# source_eagle.net
KiCad netlist of a schematic drawn in EAGLE
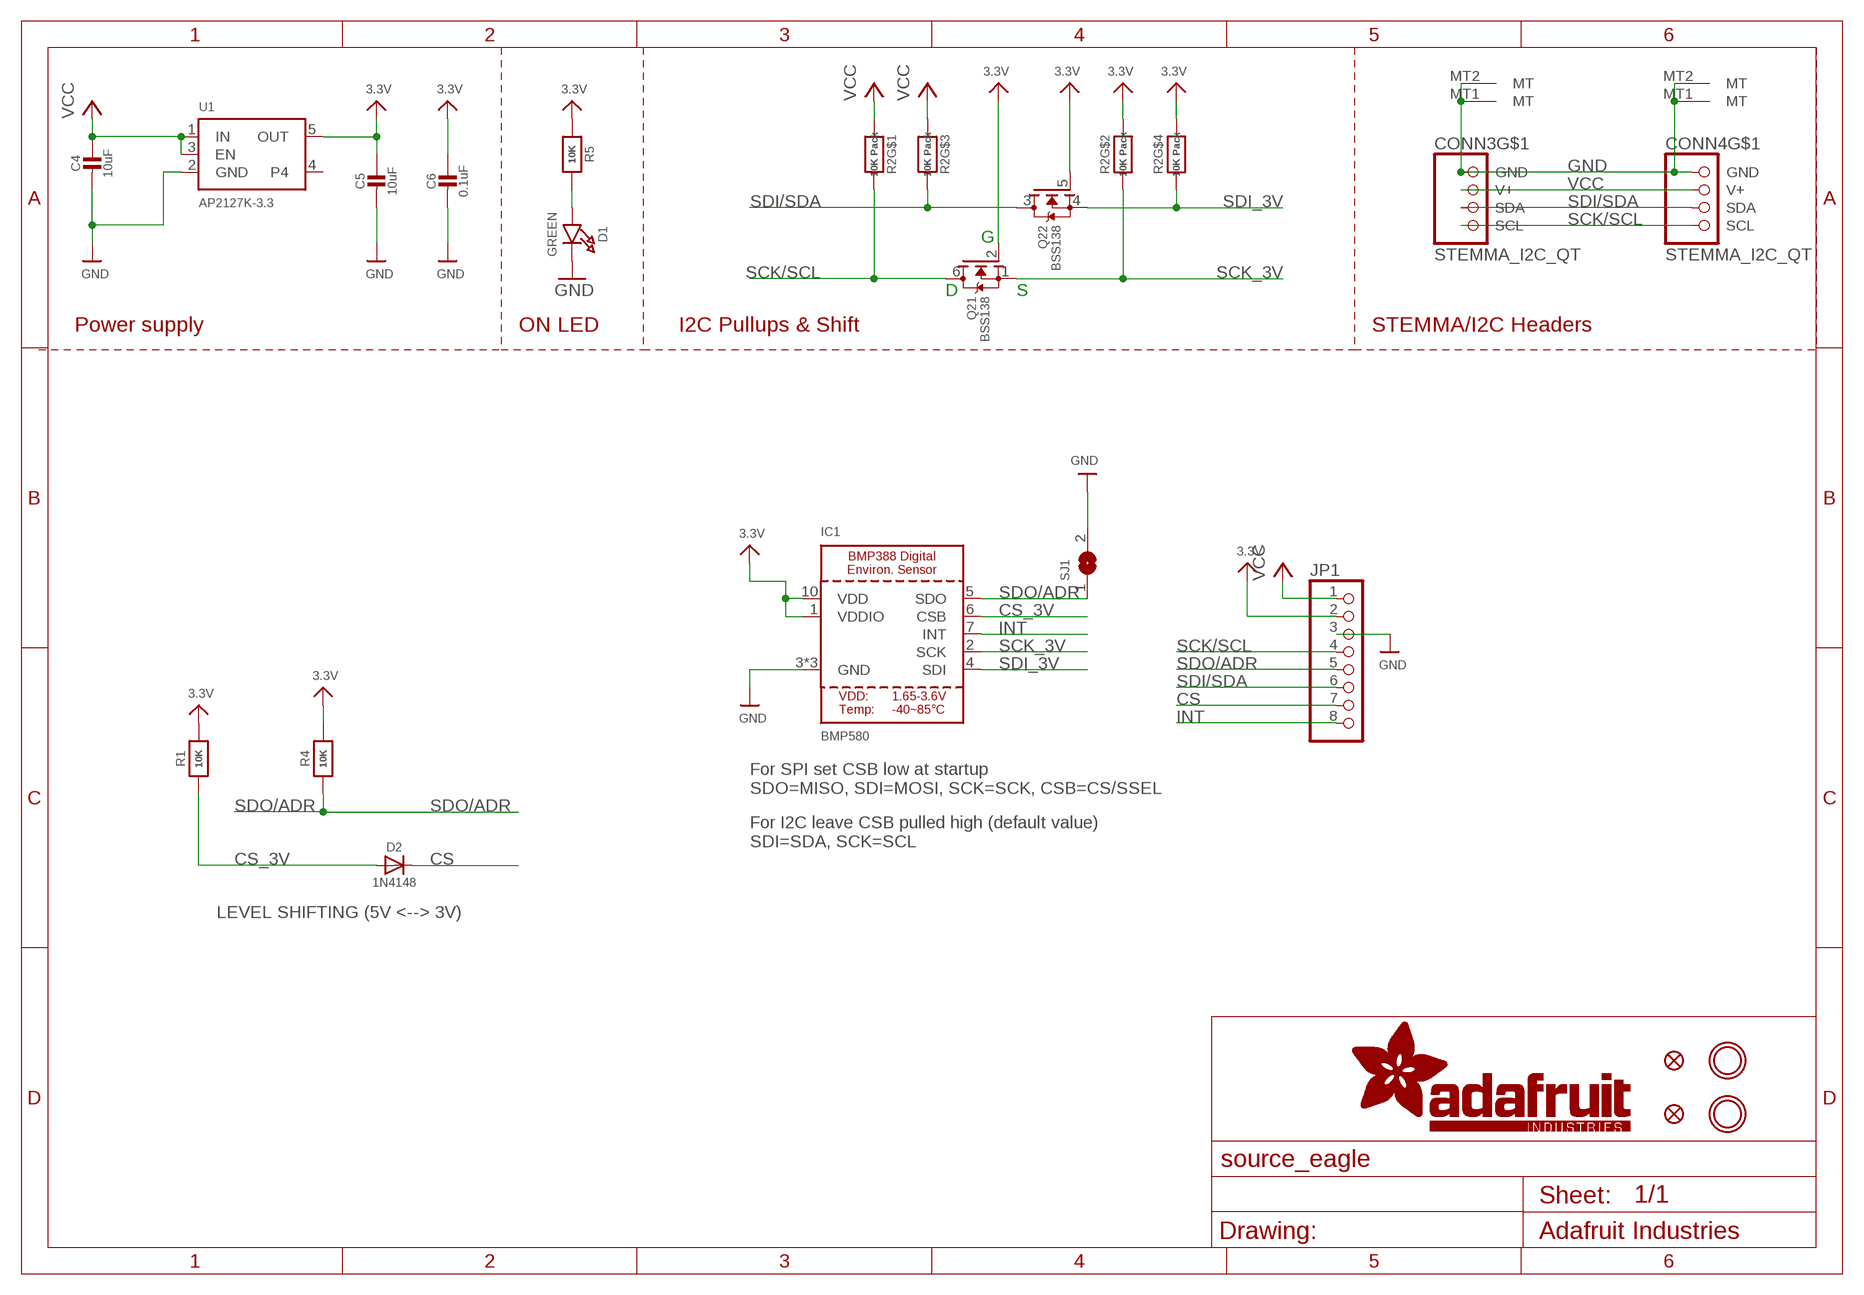
[diagram p0: schematic, sheet 1]

(export (version "E")
  (design (tool "Eeschema 10.0.6"))
  (components
    (comp (ref "C4")
      (value "10uF")
      (footprint "eagle-import:0805-NO")
      (libsource (lib "eagle-import") (part "CAP_CERAMIC0805-NOOUTLINE"))
    )
    (comp (ref "C5")
      (value "10uF")
      (footprint "eagle-import:0805-NO")
      (libsource (lib "eagle-import") (part "CAP_CERAMIC0805-NOOUTLINE"))
    )
    (comp (ref "C6")
      (value "0.1uF")
      (footprint "eagle-import:0603-NO")
      (libsource (lib "eagle-import") (part "CAP_CERAMIC0603_NO"))
    )
    (comp (ref "CONN3")
      (value "STEMMA_I2C_QT")
      (footprint "eagle-import:JST_SH4")
      (libsource (lib "eagle-import") (part "STEMMA_I2C_QT"))
    )
    (comp (ref "CONN4")
      (value "STEMMA_I2C_QT")
      (footprint "eagle-import:JST_SH4")
      (libsource (lib "eagle-import") (part "STEMMA_I2C_QT"))
    )
    (comp (ref "D1")
      (value "GREEN")
      (footprint "eagle-import:CHIPLED_0603_NOOUTLINE")
      (libsource (lib "eagle-import") (part "LED0603_NOOUTLINE"))
    )
    (comp (ref "D2")
      (value "1N4148")
      (footprint "eagle-import:SOD-323")
      (libsource (lib "eagle-import") (part "DIODESOD-323"))
    )
    (comp (ref "FID3")
      (value "FIDUCIAL_1MM")
      (footprint "eagle-import:FIDUCIAL_1MM")
      (libsource (lib "eagle-import") (part "FIDUCIAL_1MM"))
    )
    (comp (ref "FID4")
      (value "FIDUCIAL_1MM")
      (footprint "eagle-import:FIDUCIAL_1MM")
      (libsource (lib "eagle-import") (part "FIDUCIAL_1MM"))
    )
    (comp (ref "IC1")
      (value "BMP580")
      (footprint "eagle-import:BMP388")
      (libsource (lib "eagle-import") (part "BMP388"))
    )
    (comp (ref "JP1")
      (value "HEADER-1X870MIL")
      (footprint "eagle-import:1X08_ROUND_70")
      (libsource (lib "eagle-import") (part "HEADER-1X870MIL"))
    )
    (comp (ref "Q2")
      (value "BSS138")
      (footprint "eagle-import:SOT363")
      (libsource (lib "eagle-import") (part "MOSFET-N_DUAL"))
    )
    (comp (ref "R1")
      (value "10K")
      (footprint "eagle-import:0603-NO")
      (libsource (lib "eagle-import") (part "RESISTOR_0603_NOOUT"))
    )
    (comp (ref "R2")
      (value "10K Pack")
      (footprint "eagle-import:RESPACK_4X0603")
      (libsource (lib "eagle-import") (part "RESISTOR_4PACK"))
    )
    (comp (ref "R4")
      (value "10K")
      (footprint "eagle-import:0603-NO")
      (libsource (lib "eagle-import") (part "RESISTOR_0603_NOOUT"))
    )
    (comp (ref "R5")
      (value "10K")
      (footprint "eagle-import:0603-NO")
      (libsource (lib "eagle-import") (part "RESISTOR_0603_NOOUT"))
    )
    (comp (ref "SJ1")
      (value "SOLDERJUMPER")
      (footprint "eagle-import:SOLDERJUMPER_ARROW_NOPASTE")
      (libsource (lib "eagle-import") (part "SOLDERJUMPER"))
    )
    (comp (ref "U$40")
      (value "MOUNTINGHOLE2.5")
      (footprint "eagle-import:MOUNTINGHOLE_2.5_PLATED")
      (libsource (lib "eagle-import") (part "MOUNTINGHOLE2.5"))
    )
    (comp (ref "U$41")
      (value "MOUNTINGHOLE2.5")
      (footprint "eagle-import:MOUNTINGHOLE_2.5_PLATED")
      (libsource (lib "eagle-import") (part "MOUNTINGHOLE2.5"))
    )
    (comp (ref "U1")
      (value "AP2127K-3.3")
      (footprint "eagle-import:SOT23-5")
      (libsource (lib "eagle-import") (part "VREG_SOT23-5"))
    )
  )
  (nets
    (net (code "1") (name "/CS") (class "Default")
      (node (ref "D2") (pin "C") (pinfunction "C_C") (pintype "passive"))
      (node (ref "JP1") (pin "7") (pinfunction "7_7") (pintype "passive"))
    )
    (net (code "2") (name "/CS_3V") (class "Default")
      (node (ref "D2") (pin "A") (pinfunction "A_A") (pintype "passive"))
      (node (ref "IC1") (pin "6") (pinfunction "CSB_6") (pintype "input"))
      (node (ref "R1") (pin "1") (pinfunction "1_1") (pintype "passive"))
    )
    (net (code "3") (name "/INT") (class "Default")
      (node (ref "IC1") (pin "7") (pinfunction "INT_7") (pintype "output"))
      (node (ref "JP1") (pin "8") (pinfunction "8_8") (pintype "passive"))
    )
    (net (code "4") (name "/SCK_3V") (class "Default")
      (node (ref "IC1") (pin "2") (pinfunction "SCK_2") (pintype "input"))
      (node (ref "Q2") (pin "1") (pinfunction "S_1") (pintype "bidirectional"))
      (node (ref "R2") (pin "7") (pinfunction "2_7") (pintype "passive"))
    )
    (net (code "5") (name "/SCK{slash}SCL") (class "Default")
      (node (ref "CONN3") (pin "4") (pinfunction "SCL_4") (pintype "passive"))
      (node (ref "CONN4") (pin "4") (pinfunction "SCL_4") (pintype "passive"))
      (node (ref "JP1") (pin "4") (pinfunction "4_4") (pintype "passive"))
      (node (ref "Q2") (pin "6") (pinfunction "D_6") (pintype "bidirectional"))
      (node (ref "R2") (pin "8") (pinfunction "2_8") (pintype "passive"))
    )
    (net (code "6") (name "/SDI_3V") (class "Default")
      (node (ref "IC1") (pin "4") (pinfunction "SDI_4") (pintype "input"))
      (node (ref "Q2") (pin "4") (pinfunction "S_4") (pintype "bidirectional"))
      (node (ref "R2") (pin "5") (pinfunction "2_5") (pintype "passive"))
    )
    (net (code "7") (name "/SDI{slash}SDA") (class "Default")
      (node (ref "CONN3") (pin "3") (pinfunction "SDA_3") (pintype "passive"))
      (node (ref "CONN4") (pin "3") (pinfunction "SDA_3") (pintype "passive"))
      (node (ref "JP1") (pin "6") (pinfunction "6_6") (pintype "passive"))
      (node (ref "Q2") (pin "3") (pinfunction "D_3") (pintype "bidirectional"))
      (node (ref "R2") (pin "6") (pinfunction "2_6") (pintype "passive"))
    )
    (net (code "8") (name "/SDO{slash}ADR") (class "Default")
      (node (ref "IC1") (pin "5") (pinfunction "SDO_5") (pintype "output"))
      (node (ref "JP1") (pin "5") (pinfunction "5_5") (pintype "passive"))
      (node (ref "R4") (pin "1") (pinfunction "1_1") (pintype "passive"))
      (node (ref "SJ1") (pin "1") (pinfunction "1_1") (pintype "passive"))
    )
    (net (code "9") (name "3.3V") (class "Default")
      (node (ref "C5") (pin "1") (pinfunction "1_1") (pintype "passive"))
      (node (ref "C6") (pin "1") (pinfunction "1_1") (pintype "passive"))
      (node (ref "IC1") (pin "1") (pinfunction "VDDIO_1") (pintype "power_in"))
      (node (ref "IC1") (pin "10") (pinfunction "VDD_10") (pintype "power_in"))
      (node (ref "JP1") (pin "2") (pinfunction "2_2") (pintype "passive"))
      (node (ref "Q2") (pin "2") (pinfunction "G_2") (pintype "bidirectional"))
      (node (ref "Q2") (pin "5") (pinfunction "G_5") (pintype "bidirectional"))
      (node (ref "R1") (pin "2") (pinfunction "2_2") (pintype "passive"))
      (node (ref "R2") (pin "2") (pinfunction "1_2") (pintype "passive"))
      (node (ref "R2") (pin "4") (pinfunction "1_4") (pintype "passive"))
      (node (ref "R4") (pin "2") (pinfunction "2_2") (pintype "passive"))
      (node (ref "R5") (pin "1") (pinfunction "1_1") (pintype "passive"))
      (node (ref "U1") (pin "5") (pinfunction "OUT_5") (pintype "power_in"))
    )
    (net (code "10") (name "GND") (class "Default")
      (node (ref "C4") (pin "2") (pinfunction "2_2") (pintype "passive"))
      (node (ref "C5") (pin "2") (pinfunction "2_2") (pintype "passive"))
      (node (ref "C6") (pin "2") (pinfunction "2_2") (pintype "passive"))
      (node (ref "CONN3") (pin "1") (pinfunction "GND_1") (pintype "passive"))
      (node (ref "CONN3") (pin "MT1") (pinfunction "MT_MT1") (pintype "bidirectional"))
      (node (ref "CONN3") (pin "MT2") (pinfunction "MT_MT2") (pintype "bidirectional"))
      (node (ref "CONN4") (pin "1") (pinfunction "GND_1") (pintype "passive"))
      (node (ref "CONN4") (pin "MT1") (pinfunction "MT_MT1") (pintype "bidirectional"))
      (node (ref "CONN4") (pin "MT2") (pinfunction "MT_MT2") (pintype "bidirectional"))
      (node (ref "D1") (pin "C") (pinfunction "C_C") (pintype "passive"))
      (node (ref "IC1") (pin "3") (pinfunction "GND_3") (pintype "power_in"))
      (node (ref "IC1") (pin "8") (pinfunction "GND_8") (pintype "power_in"))
      (node (ref "IC1") (pin "9") (pinfunction "GND_9") (pintype "power_in"))
      (node (ref "JP1") (pin "3") (pinfunction "3_3") (pintype "passive"))
      (node (ref "SJ1") (pin "2") (pinfunction "2_2") (pintype "passive"))
      (node (ref "U1") (pin "2") (pinfunction "GND_2") (pintype "power_in"))
    )
    (net (code "11") (name "Net-(D1-PadA)") (class "Default")
      (node (ref "D1") (pin "A") (pinfunction "A_A") (pintype "passive"))
      (node (ref "R5") (pin "2") (pinfunction "2_2") (pintype "passive"))
    )
    (net (code "12") (name "VCC") (class "Default")
      (node (ref "C4") (pin "1") (pinfunction "1_1") (pintype "passive"))
      (node (ref "CONN3") (pin "2") (pinfunction "V+_2") (pintype "passive"))
      (node (ref "CONN4") (pin "2") (pinfunction "V+_2") (pintype "passive"))
      (node (ref "JP1") (pin "1") (pinfunction "1_1") (pintype "passive"))
      (node (ref "R2") (pin "1") (pinfunction "1_1") (pintype "passive"))
      (node (ref "R2") (pin "3") (pinfunction "1_3") (pintype "passive"))
      (node (ref "U1") (pin "1") (pinfunction "IN_1") (pintype "power_in"))
      (node (ref "U1") (pin "3") (pinfunction "EN_3") (pintype "input"))
    )
    (net (code "13") (name "unconnected-(U1-P4-Pad4)") (class "Default")
      (node (ref "U1") (pin "4") (pinfunction "P4_4") (pintype "bidirectional"))
    )
  )
)
